# science_task.net
KiCad netlist of a schematic drawn in EAGLE
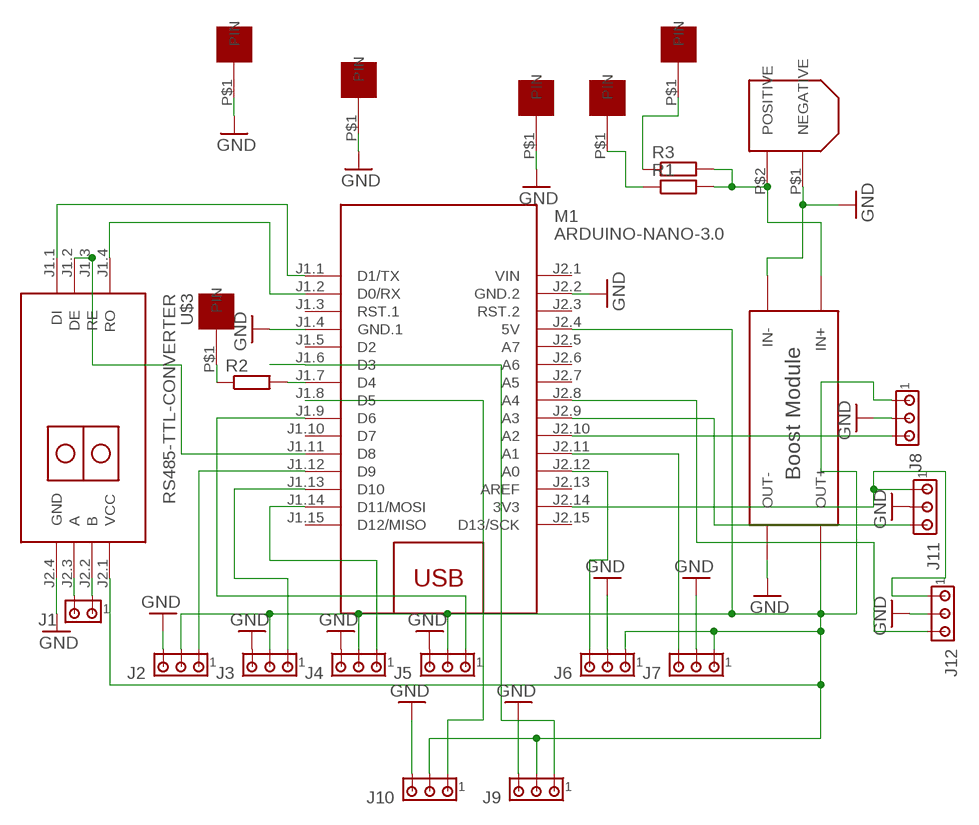
[diagram p0: schematic, sheet 1]

(export (version "E")
  (design (tool "Eeschema 10.0.6"))
  (components
    (comp (ref "J1")
      (value "MTA02-100")
      (footprint "eagle-import:10X02MTA")
      (libsource (lib "eagle-import") (part "MTA02-100"))
    )
    (comp (ref "J2")
      (value "MTA03-100")
      (footprint "eagle-import:10X03MTA")
      (libsource (lib "eagle-import") (part "MTA03-100"))
    )
    (comp (ref "J3")
      (value "MTA03-100")
      (footprint "eagle-import:10X03MTA")
      (libsource (lib "eagle-import") (part "MTA03-100"))
    )
    (comp (ref "J4")
      (value "MTA03-100")
      (footprint "eagle-import:10X03MTA")
      (libsource (lib "eagle-import") (part "MTA03-100"))
    )
    (comp (ref "J5")
      (value "MTA03-100")
      (footprint "eagle-import:10X03MTA")
      (libsource (lib "eagle-import") (part "MTA03-100"))
    )
    (comp (ref "J6")
      (value "MTA03-100")
      (footprint "eagle-import:10X03MTA")
      (libsource (lib "eagle-import") (part "MTA03-100"))
    )
    (comp (ref "J7")
      (value "MTA03-100")
      (footprint "eagle-import:10X03MTA")
      (libsource (lib "eagle-import") (part "MTA03-100"))
    )
    (comp (ref "J8")
      (value "MTA03-100")
      (footprint "eagle-import:10X03MTA")
      (libsource (lib "eagle-import") (part "MTA03-100"))
    )
    (comp (ref "J9")
      (value "MTA03-100")
      (footprint "eagle-import:10X03MTA")
      (libsource (lib "eagle-import") (part "MTA03-100"))
    )
    (comp (ref "J10")
      (value "MTA03-100")
      (footprint "eagle-import:10X03MTA")
      (libsource (lib "eagle-import") (part "MTA03-100"))
    )
    (comp (ref "J11")
      (value "MTA03-100")
      (footprint "eagle-import:10X03MTA")
      (libsource (lib "eagle-import") (part "MTA03-100"))
    )
    (comp (ref "J12")
      (value "MTA03-100")
      (footprint "eagle-import:10X03MTA")
      (libsource (lib "eagle-import") (part "MTA03-100"))
    )
    (comp (ref "M1")
      (value "ARDUINO-NANO-3.0")
      (footprint "eagle-import:ARDUINO-NANO-3.0")
      (libsource (lib "eagle-import") (part "ARDUINO-NANO-3.0"))
    )
    (comp (ref "R1")
      (value "R-EU_0204/7")
      (footprint "eagle-import:0204_7")
      (libsource (lib "eagle-import") (part "R-EU_0204/7"))
    )
    (comp (ref "R2")
      (value "R-EU_0204/7")
      (footprint "eagle-import:0204_7")
      (libsource (lib "eagle-import") (part "R-EU_0204/7"))
    )
    (comp (ref "R3")
      (value "R-EU_0204/7")
      (footprint "eagle-import:0204_7")
      (libsource (lib "eagle-import") (part "R-EU_0204/7"))
    )
    (comp (ref "U$1")
      (value "XT60")
      (footprint "eagle-import:CONNECTOR")
      (libsource (lib "eagle-import") (part "XT60"))
    )
    (comp (ref "U$2")
      (value "BOOST_MODULE")
      (footprint "eagle-import:BOOST_MODULE")
      (libsource (lib "eagle-import") (part "BOOST_MODULE"))
    )
    (comp (ref "U$3")
      (value "RS485-TTL-CONVERTER")
      (footprint "eagle-import:RS485-TTL-CONVERTER")
      (libsource (lib "eagle-import") (part "RS485-TTL-CONVERTER"))
    )
    (comp (ref "U$4")
      (value "VIA")
      (footprint "eagle-import:VIA")
      (libsource (lib "eagle-import") (part "VIA"))
    )
    (comp (ref "U$5")
      (value "VIA")
      (footprint "eagle-import:VIA")
      (libsource (lib "eagle-import") (part "VIA"))
    )
    (comp (ref "U$6")
      (value "VIA")
      (footprint "eagle-import:VIA")
      (libsource (lib "eagle-import") (part "VIA"))
    )
    (comp (ref "U$7")
      (value "VIA")
      (footprint "eagle-import:VIA")
      (libsource (lib "eagle-import") (part "VIA"))
    )
    (comp (ref "U$8")
      (value "VIA")
      (footprint "eagle-import:VIA")
      (libsource (lib "eagle-import") (part "VIA"))
    )
    (comp (ref "U$9")
      (value "VIA")
      (footprint "eagle-import:VIA")
      (libsource (lib "eagle-import") (part "VIA"))
    )
  )
  (nets
    (net (code "1") (name "/VIN") (class "Default")
      (node (ref "M1") (pin "J2.1") (pinfunction "VIN_J2.1") (pintype "power_in"))
    )
    (net (code "2") (name "GND") (class "Default")
      (node (ref "J10") (pin "3") (pinfunction "3_3") (pintype "passive"))
      (node (ref "J11") (pin "2") (pinfunction "2_2") (pintype "passive"))
      (node (ref "J12") (pin "2") (pinfunction "2_2") (pintype "passive"))
      (node (ref "J2") (pin "3") (pinfunction "3_3") (pintype "passive"))
      (node (ref "J3") (pin "3") (pinfunction "3_3") (pintype "passive"))
      (node (ref "J4") (pin "3") (pinfunction "3_3") (pintype "passive"))
      (node (ref "J5") (pin "3") (pinfunction "3_3") (pintype "passive"))
      (node (ref "J6") (pin "2") (pinfunction "2_2") (pintype "passive"))
      (node (ref "J7") (pin "2") (pinfunction "2_2") (pintype "passive"))
      (node (ref "J8") (pin "2") (pinfunction "2_2") (pintype "passive"))
      (node (ref "J9") (pin "3") (pinfunction "3_3") (pintype "passive"))
      (node (ref "M1") (pin "J1.4") (pinfunction "GND.1_J1.4") (pintype "power_in"))
      (node (ref "M1") (pin "J2.2") (pinfunction "GND.2_J2.2") (pintype "power_in"))
      (node (ref "U$1") (pin "P$1") (pinfunction "NEGATIVE_P$1") (pintype "bidirectional"))
      (node (ref "U$2") (pin "IN-") (pinfunction "IN-_IN-") (pintype "bidirectional"))
      (node (ref "U$2") (pin "OUT-") (pinfunction "OUT-_OUT-") (pintype "bidirectional"))
      (node (ref "U$3") (pin "J2.4") (pinfunction "GND_J2.4") (pintype "power_in"))
      (node (ref "U$5") (pin "P$1") (pinfunction "PIN_P$1") (pintype "bidirectional"))
      (node (ref "U$7") (pin "P$1") (pinfunction "PIN_P$1") (pintype "bidirectional"))
      (node (ref "U$9") (pin "P$1") (pinfunction "PIN_P$1") (pintype "bidirectional"))
    )
    (net (code "3") (name "Net-(M1-3V3)") (class "Default")
      (node (ref "J11") (pin "1") (pinfunction "1_1") (pintype "passive"))
      (node (ref "J12") (pin "1") (pinfunction "1_1") (pintype "passive"))
      (node (ref "M1") (pin "J2.14") (pinfunction "3V3_J2.14") (pintype "power_in"))
    )
    (net (code "4") (name "Net-(M1-5V)") (class "Default")
      (node (ref "J10") (pin "2") (pinfunction "2_2") (pintype "passive"))
      (node (ref "J2") (pin "2") (pinfunction "2_2") (pintype "passive"))
      (node (ref "J3") (pin "2") (pinfunction "2_2") (pintype "passive"))
      (node (ref "J4") (pin "2") (pinfunction "2_2") (pintype "passive"))
      (node (ref "J5") (pin "2") (pinfunction "2_2") (pintype "passive"))
      (node (ref "J6") (pin "1") (pinfunction "1_1") (pintype "passive"))
      (node (ref "J7") (pin "1") (pinfunction "1_1") (pintype "passive"))
      (node (ref "J8") (pin "1") (pinfunction "1_1") (pintype "passive"))
      (node (ref "J9") (pin "2") (pinfunction "2_2") (pintype "passive"))
      (node (ref "M1") (pin "J2.4") (pinfunction "5V_J2.4") (pintype "power_in"))
      (node (ref "U$2") (pin "OUT+") (pinfunction "OUT+_OUT+") (pintype "bidirectional"))
      (node (ref "U$3") (pin "J2.1") (pinfunction "VCC_J2.1") (pintype "power_in"))
    )
    (net (code "5") (name "Net-(M1-A0)") (class "Default")
      (node (ref "J6") (pin "3") (pinfunction "3_3") (pintype "passive"))
      (node (ref "M1") (pin "J2.12") (pinfunction "A0_J2.12") (pintype "bidirectional"))
    )
    (net (code "6") (name "Net-(M1-A1)") (class "Default")
      (node (ref "J7") (pin "3") (pinfunction "3_3") (pintype "passive"))
      (node (ref "M1") (pin "J2.11") (pinfunction "A1_J2.11") (pintype "bidirectional"))
    )
    (net (code "7") (name "Net-(M1-A2)") (class "Default")
      (node (ref "J8") (pin "3") (pinfunction "3_3") (pintype "passive"))
      (node (ref "M1") (pin "J2.10") (pinfunction "A2_J2.10") (pintype "bidirectional"))
    )
    (net (code "8") (name "Net-(M1-A3)") (class "Default")
      (node (ref "J11") (pin "3") (pinfunction "3_3") (pintype "passive"))
      (node (ref "M1") (pin "J2.9") (pinfunction "A3_J2.9") (pintype "bidirectional"))
    )
    (net (code "9") (name "Net-(M1-A4)") (class "Default")
      (node (ref "J12") (pin "3") (pinfunction "3_3") (pintype "passive"))
      (node (ref "M1") (pin "J2.8") (pinfunction "A4_J2.8") (pintype "bidirectional"))
    )
    (net (code "10") (name "Net-(M1-D0{slash}RX)") (class "Default")
      (node (ref "M1") (pin "J1.2") (pinfunction "D0/RX_J1.2") (pintype "bidirectional"))
      (node (ref "U$3") (pin "J1.4") (pinfunction "RO_J1.4") (pintype "passive"))
    )
    (net (code "11") (name "Net-(M1-D1{slash}TX)") (class "Default")
      (node (ref "M1") (pin "J1.1") (pinfunction "D1/TX_J1.1") (pintype "bidirectional"))
      (node (ref "U$3") (pin "J1.1") (pinfunction "DI_J1.1") (pintype "passive"))
    )
    (net (code "12") (name "Net-(M1-D3)") (class "Default")
      (node (ref "J9") (pin "1") (pinfunction "1_1") (pintype "passive"))
      (node (ref "M1") (pin "J1.6") (pinfunction "D3_J1.6") (pintype "bidirectional"))
    )
    (net (code "13") (name "Net-(M1-D4)") (class "Default")
      (node (ref "M1") (pin "J1.7") (pinfunction "D4_J1.7") (pintype "bidirectional"))
      (node (ref "R2") (pin "2") (pinfunction "2_2") (pintype "passive"))
    )
    (net (code "14") (name "Net-(M1-D5)") (class "Default")
      (node (ref "J10") (pin "1") (pinfunction "1_1") (pintype "passive"))
      (node (ref "M1") (pin "J1.8") (pinfunction "D5_J1.8") (pintype "bidirectional"))
    )
    (net (code "15") (name "Net-(M1-D6)") (class "Default")
      (node (ref "J5") (pin "1") (pinfunction "1_1") (pintype "passive"))
      (node (ref "M1") (pin "J1.9") (pinfunction "D6_J1.9") (pintype "bidirectional"))
    )
    (net (code "16") (name "Net-(M1-D8)") (class "Default")
      (node (ref "M1") (pin "J1.11") (pinfunction "D8_J1.11") (pintype "bidirectional"))
      (node (ref "U$3") (pin "J1.2") (pinfunction "DE_J1.2") (pintype "passive"))
      (node (ref "U$3") (pin "J1.3") (pinfunction "RE_J1.3") (pintype "passive"))
    )
    (net (code "17") (name "Net-(M1-D9)") (class "Default")
      (node (ref "J2") (pin "1") (pinfunction "1_1") (pintype "passive"))
      (node (ref "M1") (pin "J1.12") (pinfunction "D9_J1.12") (pintype "bidirectional"))
    )
    (net (code "18") (name "Net-(M1-D10)") (class "Default")
      (node (ref "J3") (pin "1") (pinfunction "1_1") (pintype "passive"))
      (node (ref "M1") (pin "J1.13") (pinfunction "D10_J1.13") (pintype "bidirectional"))
    )
    (net (code "19") (name "Net-(M1-D11{slash}MOSI)") (class "Default")
      (node (ref "J4") (pin "1") (pinfunction "1_1") (pintype "passive"))
      (node (ref "M1") (pin "J1.14") (pinfunction "D11/MOSI_J1.14") (pintype "bidirectional"))
    )
    (net (code "20") (name "Net-(U$1-POSITIVE)") (class "Default")
      (node (ref "R1") (pin "2") (pinfunction "2_2") (pintype "passive"))
      (node (ref "R3") (pin "2") (pinfunction "2_2") (pintype "passive"))
      (node (ref "U$1") (pin "P$2") (pinfunction "POSITIVE_P$2") (pintype "bidirectional"))
      (node (ref "U$2") (pin "IN+") (pinfunction "IN+_IN+") (pintype "bidirectional"))
    )
    (net (code "21") (name "Net-(U$3-A)") (class "Default")
      (node (ref "J1") (pin "2") (pinfunction "2_2") (pintype "passive"))
      (node (ref "U$3") (pin "J2.3") (pinfunction "A_J2.3") (pintype "passive"))
    )
    (net (code "22") (name "Net-(U$3-B)") (class "Default")
      (node (ref "J1") (pin "1") (pinfunction "1_1") (pintype "passive"))
      (node (ref "U$3") (pin "J2.2") (pinfunction "B_J2.2") (pintype "passive"))
    )
    (net (code "23") (name "Net-(U$4-PIN)") (class "Default")
      (node (ref "R1") (pin "1") (pinfunction "1_1") (pintype "passive"))
      (node (ref "U$4") (pin "P$1") (pinfunction "PIN_P$1") (pintype "bidirectional"))
    )
    (net (code "24") (name "Net-(U$6-PIN)") (class "Default")
      (node (ref "R2") (pin "1") (pinfunction "1_1") (pintype "passive"))
      (node (ref "U$6") (pin "P$1") (pinfunction "PIN_P$1") (pintype "bidirectional"))
    )
    (net (code "25") (name "Net-(U$8-PIN)") (class "Default")
      (node (ref "R3") (pin "1") (pinfunction "1_1") (pintype "passive"))
      (node (ref "U$8") (pin "P$1") (pinfunction "PIN_P$1") (pintype "bidirectional"))
    )
    (net (code "26") (name "unconnected-(M1-A5-PadJ2.7)") (class "Default")
      (node (ref "M1") (pin "J2.7") (pinfunction "A5_J2.7") (pintype "bidirectional"))
    )
    (net (code "27") (name "unconnected-(M1-A6-PadJ2.6)") (class "Default")
      (node (ref "M1") (pin "J2.6") (pinfunction "A6_J2.6") (pintype "bidirectional"))
    )
    (net (code "28") (name "unconnected-(M1-A7-PadJ2.5)") (class "Default")
      (node (ref "M1") (pin "J2.5") (pinfunction "A7_J2.5") (pintype "bidirectional"))
    )
    (net (code "29") (name "unconnected-(M1-AREF-PadJ2.13)") (class "Default")
      (node (ref "M1") (pin "J2.13") (pinfunction "AREF_J2.13") (pintype "bidirectional"))
    )
    (net (code "30") (name "unconnected-(M1-D2-PadJ1.5)") (class "Default")
      (node (ref "M1") (pin "J1.5") (pinfunction "D2_J1.5") (pintype "bidirectional"))
    )
    (net (code "31") (name "unconnected-(M1-D7-PadJ1.10)") (class "Default")
      (node (ref "M1") (pin "J1.10") (pinfunction "D7_J1.10") (pintype "bidirectional"))
    )
    (net (code "32") (name "unconnected-(M1-D12{slash}MISO-PadJ1.15)") (class "Default")
      (node (ref "M1") (pin "J1.15") (pinfunction "D12/MISO_J1.15") (pintype "bidirectional"))
    )
    (net (code "33") (name "unconnected-(M1-D13{slash}SCK-PadJ2.15)") (class "Default")
      (node (ref "M1") (pin "J2.15") (pinfunction "D13/SCK_J2.15") (pintype "bidirectional"))
    )
    (net (code "34") (name "unconnected-(M1-RST.1-PadJ1.3)") (class "Default")
      (node (ref "M1") (pin "J1.3") (pinfunction "RST.1_J1.3") (pintype "bidirectional"))
    )
    (net (code "35") (name "unconnected-(M1-RST.2-PadJ2.3)") (class "Default")
      (node (ref "M1") (pin "J2.3") (pinfunction "RST.2_J2.3") (pintype "bidirectional"))
    )
  )
)
